# stk200_bluetooth.net
KiCad netlist of a schematic drawn in Altium Designer
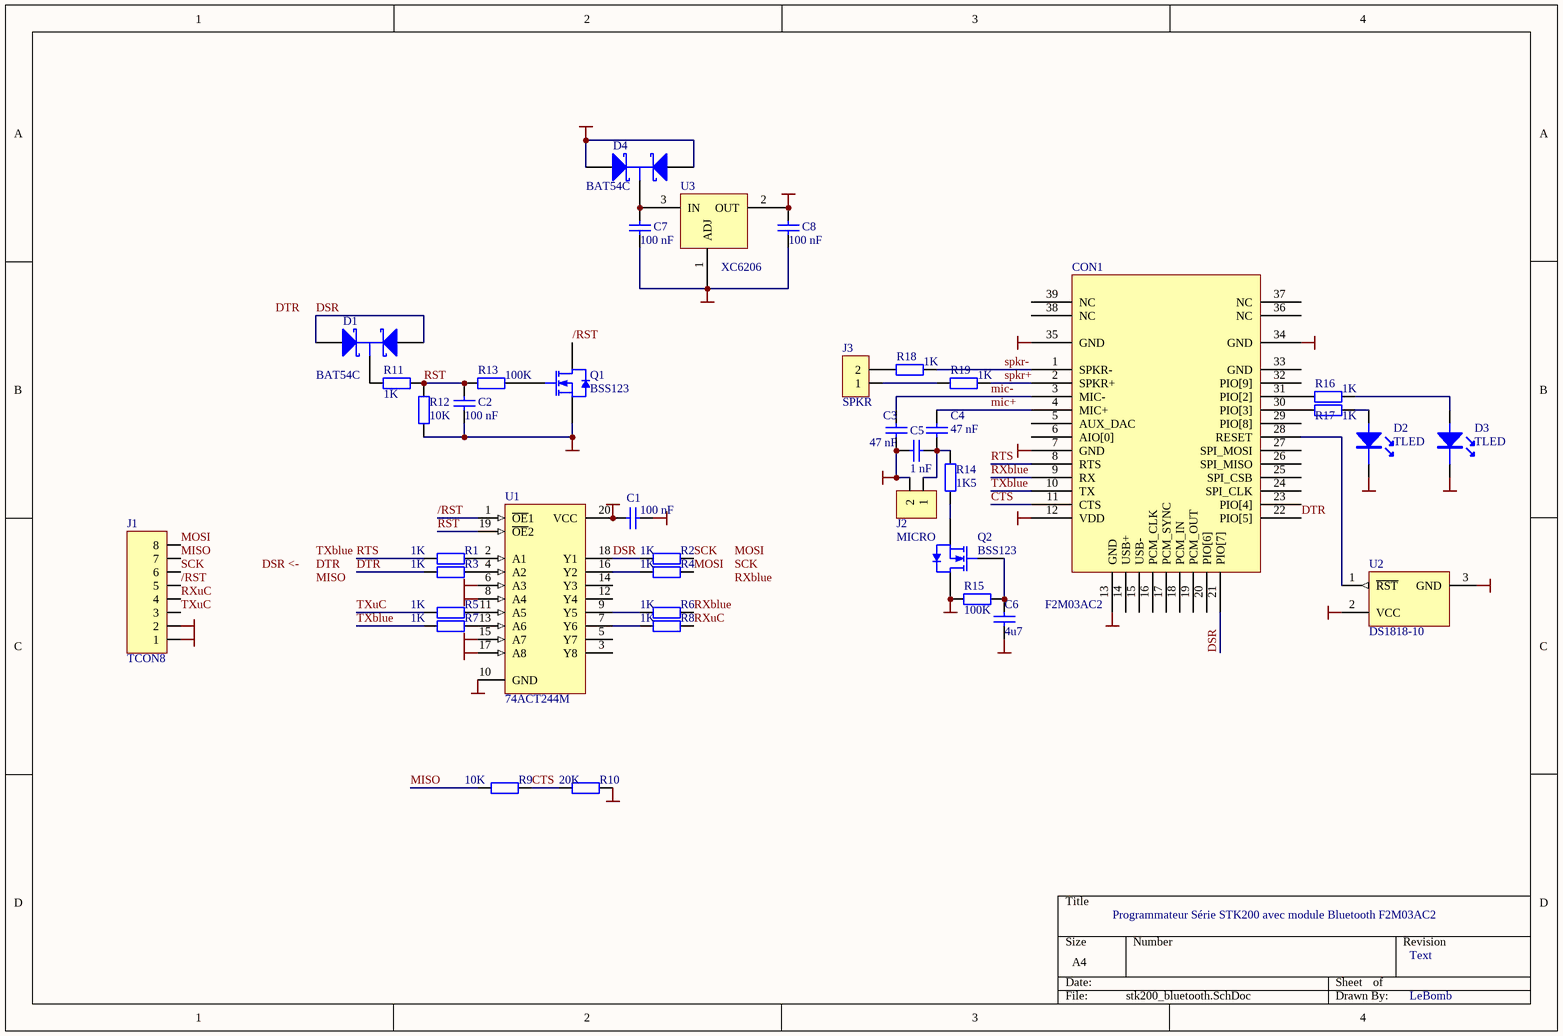
[diagram p0: stk200_bluetooth.SchDoc]

(export (version "E")
  (design (tool "Eeschema 10.0.6"))
  (components
    (comp (ref "C1")
      (value "100 nF")
      (footprint "0805")
      (description "Capacitor")
      (fields (field (name "Comment") "Cap") (field (name "PUBLISHER") "Altium Limited"))
      (libsource (lib "Miscellaneous Devices") (part "Cap"))
    )
    (comp (ref "C2")
      (value "100 nF")
      (footprint "0805")
      (description "Capacitor")
      (fields (field (name "Comment") "Cap") (field (name "PUBLISHER") "Altium Limited"))
      (libsource (lib "Miscellaneous Devices") (part "Cap"))
    )
    (comp (ref "C3")
      (value "47 nF")
      (footprint "0805")
      (description "Capacitor")
      (fields (field (name "Comment") "Cap") (field (name "PUBLISHER") "Altium Limited"))
      (libsource (lib "Miscellaneous Devices") (part "Cap"))
    )
    (comp (ref "C4")
      (value "47 nF")
      (footprint "0805")
      (description "Capacitor")
      (fields (field (name "Comment") "Cap") (field (name "PUBLISHER") "Altium Limited"))
      (libsource (lib "Miscellaneous Devices") (part "Cap"))
    )
    (comp (ref "C5")
      (value "1 nF")
      (footprint "0805")
      (description "Capacitor")
      (fields (field (name "Comment") "Cap") (field (name "PUBLISHER") "Altium Limited"))
      (libsource (lib "Miscellaneous Devices") (part "Cap"))
    )
    (comp (ref "C6")
      (value "4u7")
      (footprint "0805")
      (description "Capacitor")
      (fields (field (name "Comment") "Cap") (field (name "PUBLISHER") "Altium Limited"))
      (libsource (lib "Miscellaneous Devices") (part "Cap"))
    )
    (comp (ref "C7")
      (value "100 nF")
      (footprint "0805")
      (description "Capacitor")
      (fields (field (name "Comment") "Cap") (field (name "PUBLISHER") "Altium Limited"))
      (libsource (lib "Miscellaneous Devices") (part "Cap"))
    )
    (comp (ref "C8")
      (value "100 nF")
      (footprint "0805")
      (description "Capacitor")
      (fields (field (name "Comment") "Cap") (field (name "PUBLISHER") "Altium Limited"))
      (libsource (lib "Miscellaneous Devices") (part "Cap"))
    )
    (comp (ref "CON1")
      (value "F2M03AC2")
      (footprint "F2M03AC2_conn")
      (libsource (lib "lebomb") (part "F2M03AC2"))
    )
    (comp (ref "D1")
      (value "BAT54C")
      (footprint "SOT23")
      (description "Schottky Barrier Double Diode")
      (fields (field (name "PUBLISHER") "Altium Limited"))
      (libsource (lib "Philips Discrete Diode - Schottky") (part "BAT54C"))
    )
    (comp (ref "D2") (value "TLED") (footprint "0805") (libsource (lib "ROB03") (part "TLED")))
    (comp (ref "D3") (value "TLED") (footprint "0805") (libsource (lib "ROB03") (part "TLED")))
    (comp (ref "D4")
      (value "BAT54C")
      (footprint "SOT23")
      (description "Schottky Barrier Double Diode")
      (fields (field (name "PUBLISHER") "Altium Limited"))
      (libsource (lib "Philips Discrete Diode - Schottky") (part "BAT54C"))
    )
    (comp (ref "J1") (value "TCON8") (footprint "TSIP8") (libsource (lib "ROB04") (part "TCON8")))
    (comp (ref "J2") (value "MICRO") (footprint "CON2") (libsource (lib "") (part "CON2_1")))
    (comp (ref "J3") (value "SPKR") (footprint "CON2") (libsource (lib "*") (part "CON2")))
    (comp (ref "Q1")
      (value "BSS123")
      (footprint "SOT23")
      (description "N-channel Enhancement Mode Vertical D-MOSFET")
      (fields (field (name "PUBLISHER") "Altium Limited"))
      (libsource (lib "Philips Discrete MOSFET - Low Power") (part "BSS123"))
    )
    (comp (ref "Q2")
      (value "BSS123")
      (footprint "SOT23")
      (description "N-channel Enhancement Mode Vertical D-MOSFET")
      (fields (field (name "PUBLISHER") "Altium Limited"))
      (libsource (lib "Philips Discrete MOSFET - Low Power") (part "BSS123"))
    )
    (comp (ref "R1")
      (value "1K")
      (footprint "0805")
      (description "Resistor")
      (fields (field (name "Comment") "Res2") (field (name "PUBLISHER") "Altium Limited"))
      (libsource (lib "Miscellaneous Devices") (part "Res2"))
    )
    (comp (ref "R2")
      (value "1K")
      (footprint "0805")
      (description "Resistor")
      (fields (field (name "Comment") "Res2") (field (name "PUBLISHER") "Altium Limited"))
      (libsource (lib "Miscellaneous Devices") (part "Res2"))
    )
    (comp (ref "R3")
      (value "1K")
      (footprint "0805")
      (description "Resistor")
      (fields (field (name "Comment") "Res2") (field (name "PUBLISHER") "Altium Limited"))
      (libsource (lib "Miscellaneous Devices") (part "Res2"))
    )
    (comp (ref "R4")
      (value "1K")
      (footprint "0805")
      (description "Resistor")
      (fields (field (name "Comment") "Res2") (field (name "PUBLISHER") "Altium Limited"))
      (libsource (lib "Miscellaneous Devices") (part "Res2"))
    )
    (comp (ref "R5")
      (value "1K")
      (footprint "0805")
      (description "Resistor")
      (fields (field (name "Comment") "Res2") (field (name "PUBLISHER") "Altium Limited"))
      (libsource (lib "Miscellaneous Devices") (part "Res2"))
    )
    (comp (ref "R6")
      (value "1K")
      (footprint "0805")
      (description "Resistor")
      (fields (field (name "Comment") "Res2") (field (name "PUBLISHER") "Altium Limited"))
      (libsource (lib "Miscellaneous Devices") (part "Res2"))
    )
    (comp (ref "R7")
      (value "1K")
      (footprint "0805")
      (description "Resistor")
      (fields (field (name "Comment") "Res2") (field (name "PUBLISHER") "Altium Limited"))
      (libsource (lib "Miscellaneous Devices") (part "Res2"))
    )
    (comp (ref "R8")
      (value "1K")
      (footprint "0805")
      (description "Resistor")
      (fields (field (name "Comment") "Res2") (field (name "PUBLISHER") "Altium Limited"))
      (libsource (lib "Miscellaneous Devices") (part "Res2"))
    )
    (comp (ref "R9")
      (value "10K")
      (footprint "0805")
      (description "Resistor")
      (fields (field (name "Comment") "Res2") (field (name "PUBLISHER") "Altium Limited"))
      (libsource (lib "Miscellaneous Devices") (part "Res2"))
    )
    (comp (ref "R10")
      (value "20K")
      (footprint "0805")
      (description "Resistor")
      (fields (field (name "Comment") "Res2") (field (name "PUBLISHER") "Altium Limited"))
      (libsource (lib "Miscellaneous Devices") (part "Res2"))
    )
    (comp (ref "R11")
      (value "1K")
      (footprint "0805")
      (description "Resistor")
      (fields (field (name "Comment") "Res2") (field (name "PUBLISHER") "Altium Limited"))
      (libsource (lib "Miscellaneous Devices") (part "Res2"))
    )
    (comp (ref "R12")
      (value "10K")
      (footprint "0805")
      (description "Resistor")
      (fields (field (name "Comment") "Res2") (field (name "PUBLISHER") "Altium Limited"))
      (libsource (lib "") (part "Res2_1"))
    )
    (comp (ref "R13")
      (value "100K")
      (footprint "0805")
      (description "Resistor")
      (fields (field (name "Comment") "Res2") (field (name "PUBLISHER") "Altium Limited"))
      (libsource (lib "Miscellaneous Devices") (part "Res2"))
    )
    (comp (ref "R14")
      (value "1K5")
      (footprint "0805")
      (description "Resistor")
      (fields (field (name "Comment") "Res2") (field (name "PUBLISHER") "Altium Limited"))
      (libsource (lib "") (part "Res2_1"))
    )
    (comp (ref "R15")
      (value "100K")
      (footprint "0805")
      (description "Resistor")
      (fields (field (name "Comment") "Res2") (field (name "PUBLISHER") "Altium Limited"))
      (libsource (lib "") (part "Res2_2"))
    )
    (comp (ref "R16")
      (value "1K")
      (footprint "0805")
      (description "Resistor")
      (fields (field (name "Comment") "Res2") (field (name "PUBLISHER") "Altium Limited"))
      (libsource (lib "Miscellaneous Devices") (part "Res2"))
    )
    (comp (ref "R17")
      (value "1K")
      (footprint "0805")
      (description "Resistor")
      (fields (field (name "Comment") "Res2") (field (name "PUBLISHER") "Altium Limited"))
      (libsource (lib "Miscellaneous Devices") (part "Res2"))
    )
    (comp (ref "R18")
      (value "1K")
      (footprint "0805")
      (description "Resistor")
      (fields (field (name "Comment") "Res2") (field (name "PUBLISHER") "Altium Limited"))
      (libsource (lib "") (part "Res2_2"))
    )
    (comp (ref "R19")
      (value "1K")
      (footprint "0805")
      (description "Resistor")
      (fields (field (name "Comment") "Res2") (field (name "PUBLISHER") "Altium Limited"))
      (libsource (lib "") (part "Res2_2"))
    )
    (comp (ref "U1")
      (value "74ACT244M")
      (footprint "SO20")
      (description "Octal Bus Buffer with 3 State Outputs (Non Inverted)")
      (fields (field (name "PUBLISHER") "Altium Limited"))
      (libsource (lib "ST Logic Buffer Line Driver") (part "74ACT244M"))
    )
    (comp (ref "U2")
      (value "DS1818-10")
      (footprint "SOT-23")
      (description "3.3V EconoReset with Pushbutton")
      (fields (field (name "PUBLISHER") "Altium Limited"))
      (libsource (lib "Dallas Power Mgt Voltage Detector") (part "DS1818-10"))
    )
    (comp (ref "U3") (value "XC6206") (footprint "sot-23") (libsource (lib "ROB04") (part "LM317")))
  )
  (nets
    (net (code "1") (name "/CTS") (class "Default")
      (node (ref "CON1") (pin "11") (pinfunction "CTS_11") (pintype "passive"))
      (node (ref "R10") (pin "1") (pinfunction "1_1") (pintype "passive"))
      (node (ref "R9") (pin "2") (pinfunction "2_2") (pintype "passive"))
    )
    (net (code "2") (name "/DSR") (class "Default")
      (node (ref "CON1") (pin "21") (pinfunction "PIO[7]_21") (pintype "passive"))
      (node (ref "D1") (pin "1") (pinfunction "A1_1") (pintype "passive"))
      (node (ref "D1") (pin "2") (pinfunction "A2_2") (pintype "passive"))
      (node (ref "R2") (pin "1") (pinfunction "1_1") (pintype "passive"))
      (node (ref "U1") (pin "18") (pinfunction "Y1_18") (pintype "tri_state"))
    )
    (net (code "4") (name "/DTR") (class "Default")
      (node (ref "CON1") (pin "22") (pinfunction "PIO[5]_22") (pintype "passive"))
      (node (ref "R3") (pin "1") (pinfunction "1_1") (pintype "passive"))
    )
    (net (code "5") (name "/MISO") (class "Default")
      (node (ref "J1") (pin "7") (pinfunction "7_7") (pintype "passive"))
      (node (ref "R9") (pin "1") (pinfunction "1_1") (pintype "passive"))
    )
    (net (code "6") (name "/MOSI") (class "Default")
      (node (ref "J1") (pin "8") (pinfunction "8_8") (pintype "passive"))
      (node (ref "R4") (pin "2") (pinfunction "2_2") (pintype "passive"))
    )
    (net (code "7") (name "/RST") (class "Default")
      (node (ref "C2") (pin "2") (pinfunction "2_2") (pintype "passive"))
      (node (ref "R11") (pin "2") (pinfunction "2_2") (pintype "passive"))
      (node (ref "R12") (pin "2") (pinfunction "2_2") (pintype "passive"))
      (node (ref "R13") (pin "1") (pinfunction "1_1") (pintype "passive"))
      (node (ref "U1") (pin "19") (pinfunction "~{OE}2_19") (pintype "input"))
    )
    (net (code "8") (name "/RTS") (class "Default")
      (node (ref "CON1") (pin "8") (pinfunction "RTS_8") (pintype "passive"))
      (node (ref "R1") (pin "1") (pinfunction "1_1") (pintype "passive"))
    )
    (net (code "9") (name "/RXblue") (class "Default")
      (node (ref "CON1") (pin "9") (pinfunction "RX_9") (pintype "passive"))
      (node (ref "R6") (pin "2") (pinfunction "2_2") (pintype "passive"))
    )
    (net (code "10") (name "/RXuC") (class "Default")
      (node (ref "J1") (pin "4") (pinfunction "4_4") (pintype "passive"))
      (node (ref "R8") (pin "2") (pinfunction "2_2") (pintype "passive"))
    )
    (net (code "11") (name "/SCK") (class "Default")
      (node (ref "J1") (pin "6") (pinfunction "6_6") (pintype "passive"))
      (node (ref "R2") (pin "2") (pinfunction "2_2") (pintype "passive"))
    )
    (net (code "12") (name "/TXblue") (class "Default")
      (node (ref "CON1") (pin "10") (pinfunction "TX_10") (pintype "passive"))
      (node (ref "R7") (pin "1") (pinfunction "1_1") (pintype "passive"))
    )
    (net (code "13") (name "/TXuC") (class "Default")
      (node (ref "J1") (pin "3") (pinfunction "3_3") (pintype "passive"))
      (node (ref "R5") (pin "1") (pinfunction "1_1") (pintype "passive"))
    )
    (net (code "14") (name "/mic+") (class "Default")
      (node (ref "C4") (pin "2") (pinfunction "2_2") (pintype "passive"))
      (node (ref "CON1") (pin "4") (pinfunction "MIC+_4") (pintype "passive"))
    )
    (net (code "15") (name "/mic-") (class "Default")
      (node (ref "C3") (pin "2") (pinfunction "2_2") (pintype "passive"))
      (node (ref "CON1") (pin "3") (pinfunction "MIC-_3") (pintype "passive"))
    )
    (net (code "16") (name "/spkr+") (class "Default")
      (node (ref "CON1") (pin "2") (pinfunction "SPKR+_2") (pintype "passive"))
      (node (ref "R19") (pin "1") (pinfunction "1_1") (pintype "passive"))
    )
    (net (code "17") (name "/spkr-") (class "Default")
      (node (ref "CON1") (pin "1") (pinfunction "SPKR-_1") (pintype "passive"))
      (node (ref "R18") (pin "1") (pinfunction "1_1") (pintype "passive"))
    )
    (net (code "18") (name "/{slash}RST") (class "Default")
      (node (ref "J1") (pin "5") (pinfunction "5_5") (pintype "passive"))
      (node (ref "Q1") (pin "3") (pinfunction "D_3") (pintype "passive"))
      (node (ref "U1") (pin "1") (pinfunction "~{OE}1_1") (pintype "input"))
    )
    (net (code "19") (name "3V3") (class "Default")
      (node (ref "C1") (pin "1") (pinfunction "1_1") (pintype "passive"))
      (node (ref "C8") (pin "2") (pinfunction "2_2") (pintype "passive"))
      (node (ref "CON1") (pin "12") (pinfunction "VDD_12") (pintype "passive"))
      (node (ref "Q2") (pin "3") (pinfunction "D_3") (pintype "passive"))
      (node (ref "R15") (pin "2") (pinfunction "2_2") (pintype "passive"))
      (node (ref "U1") (pin "20") (pinfunction "VCC_20") (pintype "power_in"))
      (node (ref "U2") (pin "2") (pinfunction "VCC_2") (pintype "power_in"))
      (node (ref "U3") (pin "2") (pinfunction "OUT_2") (pintype "passive"))
    )
    (net (code "20") (name "5V") (class "Default")
      (node (ref "D4") (pin "1") (pinfunction "A1_1") (pintype "passive"))
      (node (ref "D4") (pin "2") (pinfunction "A2_2") (pintype "passive"))
      (node (ref "J1") (pin "1") (pinfunction "1_1") (pintype "passive"))
    )
    (net (code "21") (name "GND") (class "Default")
      (node (ref "C1") (pin "2") (pinfunction "2_2") (pintype "passive"))
      (node (ref "C2") (pin "1") (pinfunction "1_1") (pintype "passive"))
      (node (ref "C3") (pin "1") (pinfunction "1_1") (pintype "passive"))
      (node (ref "C5") (pin "2") (pinfunction "2_2") (pintype "passive"))
      (node (ref "C6") (pin "1") (pinfunction "1_1") (pintype "passive"))
      (node (ref "C7") (pin "1") (pinfunction "1_1") (pintype "passive"))
      (node (ref "C8") (pin "1") (pinfunction "1_1") (pintype "passive"))
      (node (ref "CON1") (pin "13") (pinfunction "GND_13") (pintype "passive"))
      (node (ref "CON1") (pin "34") (pinfunction "GND_34") (pintype "passive"))
      (node (ref "CON1") (pin "35") (pinfunction "GND_35") (pintype "passive"))
      (node (ref "CON1") (pin "7") (pinfunction "GND_7") (pintype "passive"))
      (node (ref "D2") (pin "2") (pinfunction "2_2") (pintype "passive"))
      (node (ref "D3") (pin "2") (pinfunction "2_2") (pintype "passive"))
      (node (ref "J1") (pin "2") (pinfunction "2_2") (pintype "passive"))
      (node (ref "J2") (pin "2") (pinfunction "2_2") (pintype "passive"))
      (node (ref "Q1") (pin "2") (pinfunction "S_2") (pintype "passive"))
      (node (ref "R10") (pin "2") (pinfunction "2_2") (pintype "passive"))
      (node (ref "R12") (pin "1") (pinfunction "1_1") (pintype "passive"))
      (node (ref "U1") (pin "10") (pinfunction "GND_10") (pintype "power_in"))
      (node (ref "U1") (pin "15") (pinfunction "A7_15") (pintype "input"))
      (node (ref "U1") (pin "17") (pinfunction "A8_17") (pintype "input"))
      (node (ref "U1") (pin "6") (pinfunction "A3_6") (pintype "input"))
      (node (ref "U1") (pin "8") (pinfunction "A4_8") (pintype "input"))
      (node (ref "U2") (pin "3") (pinfunction "GND_3") (pintype "power_in"))
      (node (ref "U3") (pin "1") (pinfunction "ADJ_1") (pintype "passive"))
    )
    (net (code "22") (name "Net-(C4-Pad1)") (class "Default")
      (node (ref "C4") (pin "1") (pinfunction "1_1") (pintype "passive"))
      (node (ref "C5") (pin "1") (pinfunction "1_1") (pintype "passive"))
      (node (ref "J2") (pin "1") (pinfunction "1_1") (pintype "passive"))
      (node (ref "R14") (pin "2") (pinfunction "2_2") (pintype "passive"))
    )
    (net (code "23") (name "Net-(CON1-PIO[2])") (class "Default")
      (node (ref "CON1") (pin "31") (pinfunction "PIO[2]_31") (pintype "passive"))
      (node (ref "R16") (pin "1") (pinfunction "1_1") (pintype "passive"))
    )
    (net (code "24") (name "Net-(CON1-PIO[3])") (class "Default")
      (node (ref "CON1") (pin "30") (pinfunction "PIO[3]_30") (pintype "passive"))
      (node (ref "R17") (pin "1") (pinfunction "1_1") (pintype "passive"))
    )
    (net (code "25") (name "Net-(CON1-RESET)") (class "Default")
      (node (ref "CON1") (pin "28") (pinfunction "RESET_28") (pintype "passive"))
      (node (ref "U2") (pin "1") (pinfunction "~{RST}_1") (pintype "output"))
    )
    (net (code "26") (name "Net-(D1-K)") (class "Default")
      (node (ref "D1") (pin "3") (pinfunction "K_3") (pintype "passive"))
      (node (ref "R11") (pin "1") (pinfunction "1_1") (pintype "passive"))
    )
    (net (code "27") (name "Net-(D2-Pad1)") (class "Default")
      (node (ref "D2") (pin "1") (pinfunction "1_1") (pintype "passive"))
      (node (ref "R17") (pin "2") (pinfunction "2_2") (pintype "passive"))
    )
    (net (code "28") (name "Net-(D3-Pad1)") (class "Default")
      (node (ref "D3") (pin "1") (pinfunction "1_1") (pintype "passive"))
      (node (ref "R16") (pin "2") (pinfunction "2_2") (pintype "passive"))
    )
    (net (code "29") (name "Net-(D4-K)") (class "Default")
      (node (ref "C7") (pin "2") (pinfunction "2_2") (pintype "passive"))
      (node (ref "D4") (pin "3") (pinfunction "K_3") (pintype "passive"))
      (node (ref "U3") (pin "3") (pinfunction "IN_3") (pintype "passive"))
    )
    (net (code "30") (name "Net-(J3-Pad1)") (class "Default")
      (node (ref "J3") (pin "1") (pinfunction "1_1") (pintype "passive"))
      (node (ref "R19") (pin "2") (pinfunction "2_2") (pintype "passive"))
    )
    (net (code "31") (name "Net-(J3-Pad2)") (class "Default")
      (node (ref "J3") (pin "2") (pinfunction "2_2") (pintype "passive"))
      (node (ref "R18") (pin "2") (pinfunction "2_2") (pintype "passive"))
    )
    (net (code "32") (name "Net-(Q1-G)") (class "Default")
      (node (ref "Q1") (pin "1") (pinfunction "G_1") (pintype "passive"))
      (node (ref "R13") (pin "2") (pinfunction "2_2") (pintype "passive"))
    )
    (net (code "33") (name "Net-(Q2-G)") (class "Default")
      (node (ref "C6") (pin "2") (pinfunction "2_2") (pintype "passive"))
      (node (ref "Q2") (pin "1") (pinfunction "G_1") (pintype "passive"))
      (node (ref "R15") (pin "1") (pinfunction "1_1") (pintype "passive"))
    )
    (net (code "34") (name "Net-(Q2-S)") (class "Default")
      (node (ref "Q2") (pin "2") (pinfunction "S_2") (pintype "passive"))
      (node (ref "R14") (pin "1") (pinfunction "1_1") (pintype "passive"))
    )
    (net (code "35") (name "Net-(U1-A1)") (class "Default")
      (node (ref "R1") (pin "2") (pinfunction "2_2") (pintype "passive"))
      (node (ref "U1") (pin "2") (pinfunction "A1_2") (pintype "input"))
    )
    (net (code "36") (name "Net-(U1-A2)") (class "Default")
      (node (ref "R3") (pin "2") (pinfunction "2_2") (pintype "passive"))
      (node (ref "U1") (pin "4") (pinfunction "A2_4") (pintype "input"))
    )
    (net (code "37") (name "Net-(U1-A5)") (class "Default")
      (node (ref "R5") (pin "2") (pinfunction "2_2") (pintype "passive"))
      (node (ref "U1") (pin "11") (pinfunction "A5_11") (pintype "input"))
    )
    (net (code "38") (name "Net-(U1-A6)") (class "Default")
      (node (ref "R7") (pin "2") (pinfunction "2_2") (pintype "passive"))
      (node (ref "U1") (pin "13") (pinfunction "A6_13") (pintype "input"))
    )
    (net (code "39") (name "Net-(U1-Y2)") (class "Default")
      (node (ref "R4") (pin "1") (pinfunction "1_1") (pintype "passive"))
      (node (ref "U1") (pin "16") (pinfunction "Y2_16") (pintype "tri_state"))
    )
    (net (code "40") (name "Net-(U1-Y5)") (class "Default")
      (node (ref "R6") (pin "1") (pinfunction "1_1") (pintype "passive"))
      (node (ref "U1") (pin "9") (pinfunction "Y5_9") (pintype "tri_state"))
    )
    (net (code "41") (name "Net-(U1-Y6)") (class "Default")
      (node (ref "R8") (pin "1") (pinfunction "1_1") (pintype "passive"))
      (node (ref "U1") (pin "7") (pinfunction "Y6_7") (pintype "tri_state"))
    )
    (net (code "42") (name "unconnected-(CON1-AIO[0]-Pad6)") (class "Default")
      (node (ref "CON1") (pin "6") (pinfunction "AIO[0]_6") (pintype "passive"))
    )
    (net (code "43") (name "unconnected-(CON1-AUX_DAC-Pad5)") (class "Default")
      (node (ref "CON1") (pin "5") (pinfunction "AUX_DAC_5") (pintype "passive"))
    )
    (net (code "44") (name "unconnected-(CON1-GND-Pad33)") (class "Default")
      (node (ref "CON1") (pin "33") (pinfunction "GND_33") (pintype "passive"))
    )
    (net (code "45") (name "unconnected-(CON1-NC-Pad36)") (class "Default")
      (node (ref "CON1") (pin "36") (pinfunction "NC_36") (pintype "passive"))
    )
    (net (code "46") (name "unconnected-(CON1-NC-Pad37)") (class "Default")
      (node (ref "CON1") (pin "37") (pinfunction "NC_37") (pintype "passive"))
    )
    (net (code "47") (name "unconnected-(CON1-NC-Pad38)") (class "Default")
      (node (ref "CON1") (pin "38") (pinfunction "NC_38") (pintype "passive"))
    )
    (net (code "48") (name "unconnected-(CON1-NC-Pad39)") (class "Default")
      (node (ref "CON1") (pin "39") (pinfunction "NC_39") (pintype "passive"))
    )
    (net (code "49") (name "unconnected-(CON1-PCM_CLK-Pad16)") (class "Default")
      (node (ref "CON1") (pin "16") (pinfunction "PCM_CLK_16") (pintype "passive"))
    )
    (net (code "50") (name "unconnected-(CON1-PCM_IN-Pad18)") (class "Default")
      (node (ref "CON1") (pin "18") (pinfunction "PCM_IN_18") (pintype "passive"))
    )
    (net (code "51") (name "unconnected-(CON1-PCM_OUT-Pad19)") (class "Default")
      (node (ref "CON1") (pin "19") (pinfunction "PCM_OUT_19") (pintype "passive"))
    )
    (net (code "52") (name "unconnected-(CON1-PCM_SYNC-Pad17)") (class "Default")
      (node (ref "CON1") (pin "17") (pinfunction "PCM_SYNC_17") (pintype "passive"))
    )
    (net (code "53") (name "unconnected-(CON1-PIO[4]-Pad23)") (class "Default")
      (node (ref "CON1") (pin "23") (pinfunction "PIO[4]_23") (pintype "passive"))
    )
    (net (code "54") (name "unconnected-(CON1-PIO[6]-Pad20)") (class "Default")
      (node (ref "CON1") (pin "20") (pinfunction "PIO[6]_20") (pintype "passive"))
    )
    (net (code "55") (name "unconnected-(CON1-PIO[8]-Pad29)") (class "Default")
      (node (ref "CON1") (pin "29") (pinfunction "PIO[8]_29") (pintype "passive"))
    )
    (net (code "56") (name "unconnected-(CON1-PIO[9]-Pad32)") (class "Default")
      (node (ref "CON1") (pin "32") (pinfunction "PIO[9]_32") (pintype "passive"))
    )
    (net (code "57") (name "unconnected-(CON1-SPI_CLK-Pad24)") (class "Default")
      (node (ref "CON1") (pin "24") (pinfunction "SPI_CLK_24") (pintype "passive"))
    )
    (net (code "58") (name "unconnected-(CON1-SPI_CSB-Pad25)") (class "Default")
      (node (ref "CON1") (pin "25") (pinfunction "SPI_CSB_25") (pintype "passive"))
    )
    (net (code "59") (name "unconnected-(CON1-SPI_MISO-Pad26)") (class "Default")
      (node (ref "CON1") (pin "26") (pinfunction "SPI_MISO_26") (pintype "passive"))
    )
    (net (code "60") (name "unconnected-(CON1-SPI_MOSI-Pad27)") (class "Default")
      (node (ref "CON1") (pin "27") (pinfunction "SPI_MOSI_27") (pintype "passive"))
    )
    (net (code "61") (name "unconnected-(CON1-USB+-Pad14)") (class "Default")
      (node (ref "CON1") (pin "14") (pinfunction "USB+_14") (pintype "passive"))
    )
    (net (code "62") (name "unconnected-(CON1-USB--Pad15)") (class "Default")
      (node (ref "CON1") (pin "15") (pinfunction "USB-_15") (pintype "passive"))
    )
    (net (code "63") (name "unconnected-(U1-Y3-Pad14)") (class "Default")
      (node (ref "U1") (pin "14") (pinfunction "Y3_14") (pintype "tri_state"))
    )
    (net (code "64") (name "unconnected-(U1-Y4-Pad12)") (class "Default")
      (node (ref "U1") (pin "12") (pinfunction "Y4_12") (pintype "tri_state"))
    )
    (net (code "65") (name "unconnected-(U1-Y7-Pad5)") (class "Default")
      (node (ref "U1") (pin "5") (pinfunction "Y7_5") (pintype "tri_state"))
    )
    (net (code "66") (name "unconnected-(U1-Y8-Pad3)") (class "Default")
      (node (ref "U1") (pin "3") (pinfunction "Y8_3") (pintype "tri_state"))
    )
  )
)
